# Qwiic_Haptic_Driver_DA7280.net
KiCad netlist of a schematic drawn in EAGLE
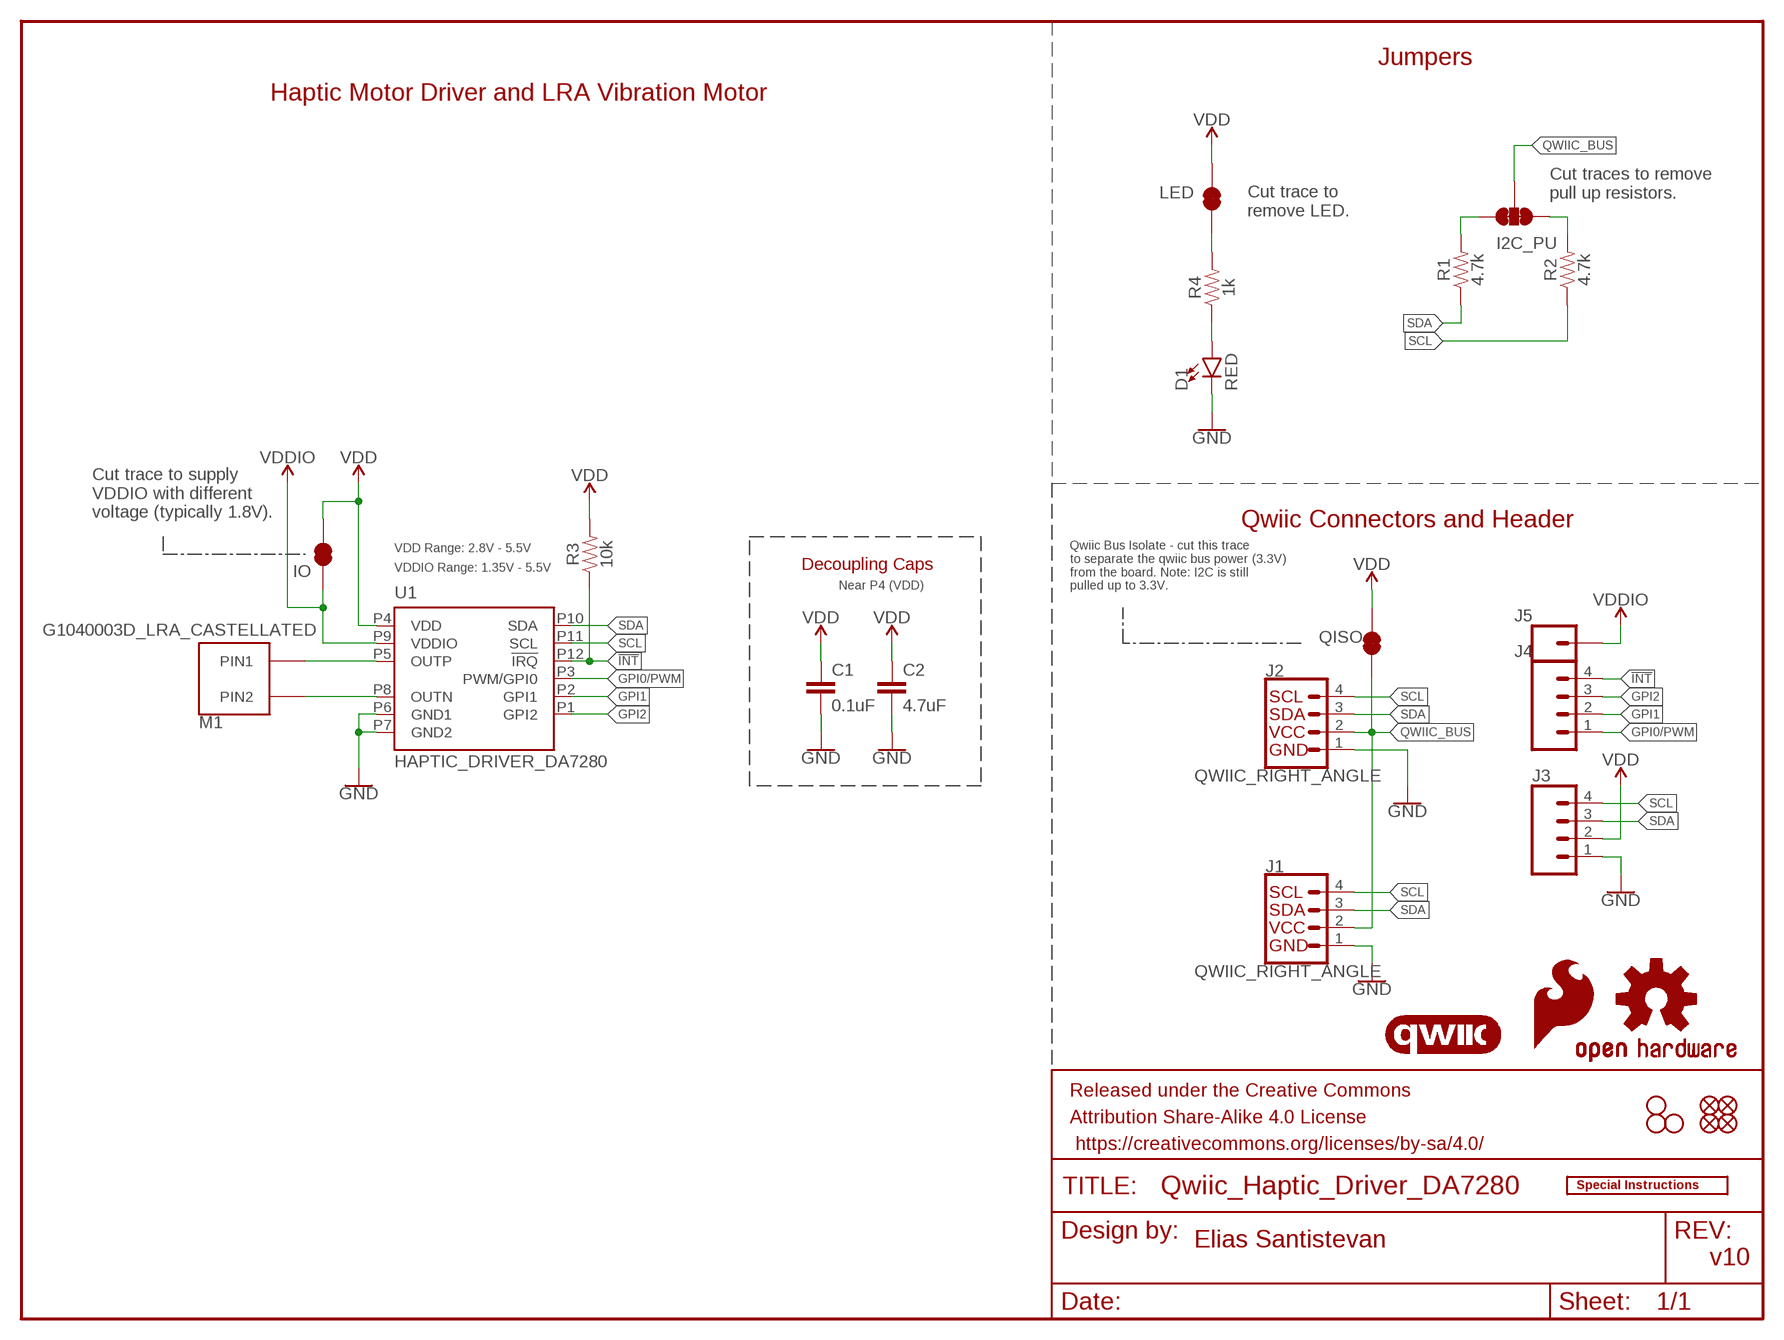
[diagram p0: schematic, sheet 1]

(export (version "E")
  (design (tool "Eeschema 10.0.6"))
  (components
    (comp (ref "C1")
      (value "0.1uF")
      (footprint "eagle-import:0603")
      (libsource (lib "eagle-import") (part "0.1UF-0603-25V-5%"))
    )
    (comp (ref "C2")
      (value "4.7uF")
      (footprint "eagle-import:0603")
      (libsource (lib "eagle-import") (part "4.7UF-0603-6.3V-(10%)"))
    )
    (comp (ref "D1")
      (value "RED")
      (footprint "eagle-import:LED-0603")
      (libsource (lib "eagle-import") (part "LED-RED0603"))
    )
    (comp (ref "FD1")
      (value "FIDUCIALUFIDUCIAL")
      (footprint "eagle-import:FIDUCIAL-MICRO")
      (libsource (lib "eagle-import") (part "FIDUCIALUFIDUCIAL"))
    )
    (comp (ref "FD2")
      (value "FIDUCIALUFIDUCIAL")
      (footprint "eagle-import:FIDUCIAL-MICRO")
      (libsource (lib "eagle-import") (part "FIDUCIALUFIDUCIAL"))
    )
    (comp (ref "FD3")
      (value "FIDUCIALUFIDUCIAL")
      (footprint "eagle-import:FIDUCIAL-MICRO")
      (libsource (lib "eagle-import") (part "FIDUCIALUFIDUCIAL"))
    )
    (comp (ref "FD4")
      (value "FIDUCIALUFIDUCIAL")
      (footprint "eagle-import:FIDUCIAL-MICRO")
      (libsource (lib "eagle-import") (part "FIDUCIALUFIDUCIAL"))
    )
    (comp (ref "FRAME1")
      (value "FRAME-LETTER")
      (footprint "eagle-import:CREATIVE_COMMONS")
      (libsource (lib "eagle-import") (part "FRAME-LETTER"))
    )
    (comp (ref "H1")
      (value "STAND-OFFTIGHT")
      (footprint "eagle-import:STAND-OFF-TIGHT")
      (libsource (lib "eagle-import") (part "STAND-OFFTIGHT"))
    )
    (comp (ref "H2")
      (value "STAND-OFFTIGHT")
      (footprint "eagle-import:STAND-OFF-TIGHT")
      (libsource (lib "eagle-import") (part "STAND-OFFTIGHT"))
    )
    (comp (ref "H4")
      (value "STAND-OFFTIGHT")
      (footprint "eagle-import:STAND-OFF-TIGHT")
      (libsource (lib "eagle-import") (part "STAND-OFFTIGHT"))
    )
    (comp (ref "J1")
      (value "QWIIC_RIGHT_ANGLE")
      (footprint "eagle-import:JST04_1MM_RA")
      (libsource (lib "eagle-import") (part "QWIIC_CONNECTORJS-1MM"))
    )
    (comp (ref "J2")
      (value "QWIIC_RIGHT_ANGLE")
      (footprint "eagle-import:JST04_1MM_RA")
      (libsource (lib "eagle-import") (part "QWIIC_CONNECTORJS-1MM"))
    )
    (comp (ref "J3")
      (value "CONN_041X04_NO_SILK_NO_POP")
      (footprint "eagle-import:1X04_NO_SILK")
      (libsource (lib "eagle-import") (part "CONN_041X04_NO_SILK_NO_POP"))
    )
    (comp (ref "J4")
      (value "CONN_041X04_NO_SILK_NO_POP")
      (footprint "eagle-import:1X04_NO_SILK")
      (libsource (lib "eagle-import") (part "CONN_041X04_NO_SILK_NO_POP"))
    )
    (comp (ref "J5")
      (value "CONN_01PTH_NO_SILK_YES_STOP")
      (footprint "eagle-import:1X01_NO_SILK")
      (libsource (lib "eagle-import") (part "CONN_01PTH_NO_SILK_YES_STOP"))
    )
    (comp (ref "JP1")
      (value "LED")
      (footprint "eagle-import:SMT-JUMPER_2_NC_TRACE_SILK")
      (libsource (lib "eagle-import") (part "JUMPER-SMT_2_NC_TRACE_SILK"))
    )
    (comp (ref "JP2")
      (value "LED")
      (footprint "eagle-import:SMT-JUMPER_2_NC_TRACE_SILK")
      (libsource (lib "eagle-import") (part "JUMPER-SMT_2_NC_TRACE_SILK"))
    )
    (comp (ref "JP3")
      (value "I2C_PU")
      (footprint "eagle-import:SMT-JUMPER_3_2-NC_TRACE_SILK")
      (libsource (lib "eagle-import") (part "JUMPER-SMT_3_2-NC_TRACE_SILK"))
    )
    (comp (ref "JP4")
      (value "LED")
      (footprint "eagle-import:SMT-JUMPER_2_NC_TRACE_SILK")
      (libsource (lib "eagle-import") (part "JUMPER-SMT_2_NC_TRACE_SILK"))
    )
    (comp (ref "LOGO1")
      (value "SPECIAL_INSTRUCTIONS-ORDERING")
      (footprint "eagle-import:ORDERING_INSTRUCTIONS")
      (libsource (lib "eagle-import") (part "SPECIAL_INSTRUCTIONS-ORDERING"))
    )
    (comp (ref "LOGO2")
      (value "OSHW-LOGOS")
      (footprint "eagle-import:OSHW-LOGO-S")
      (libsource (lib "eagle-import") (part "OSHW-LOGOS"))
    )
    (comp (ref "LOGO4")
      (value "SFE_LOGO_FLAME.1_INCH")
      (footprint "eagle-import:SFE_LOGO_FLAME_.1")
      (libsource (lib "eagle-import") (part "SFE_LOGO_FLAME.1_INCH"))
    )
    (comp (ref "M1")
      (value "G1040003D_LRA_CASTELLATED")
      (footprint "eagle-import:COIN_VIBRATION_MOTOR_CASTEL")
      (libsource (lib "eagle-import") (part "G1040003D_LRA_CASTELLATED"))
    )
    (comp (ref "R1")
      (value "4.7k")
      (footprint "eagle-import:0603")
      (libsource (lib "eagle-import") (part "4.7KOHM-0603-1/10W-1%"))
    )
    (comp (ref "R2")
      (value "4.7k")
      (footprint "eagle-import:0603")
      (libsource (lib "eagle-import") (part "4.7KOHM-0603-1/10W-1%"))
    )
    (comp (ref "R3")
      (value "10k")
      (footprint "eagle-import:0603")
      (libsource (lib "eagle-import") (part "10KOHM-0603-1/10W-1%"))
    )
    (comp (ref "R4")
      (value "1k")
      (footprint "eagle-import:0603")
      (libsource (lib "eagle-import") (part "1KOHM-0603-1/10W-1%"))
    )
    (comp (ref "U$1")
      (value "QWIIC_LOGO_3MM")
      (footprint "eagle-import:QWIIC_3MM")
      (libsource (lib "eagle-import") (part "QWIIC_LOGO_3MM"))
    )
    (comp (ref "U1")
      (value "HAPTIC_DRIVER_DA7280")
      (footprint "eagle-import:QFN_DA7280")
      (libsource (lib "eagle-import") (part "HAPTIC_DRIVER_DA7280"))
    )
  )
  (nets
    (net (code "1") (name "/~{INT}") (class "Default")
      (node (ref "J4") (pin "4") (pinfunction "4_4") (pintype "passive"))
      (node (ref "R3") (pin "1") (pinfunction "1_1") (pintype "passive"))
      (node (ref "U1") (pin "P12") (pinfunction "~{IRQ}_P12") (pintype "output"))
    )
    (net (code "2") (name "GND") (class "Default")
      (node (ref "C1") (pin "2") (pinfunction "2_2") (pintype "passive"))
      (node (ref "C2") (pin "2") (pinfunction "2_2") (pintype "passive"))
      (node (ref "D1") (pin "C") (pinfunction "C_C") (pintype "passive"))
      (node (ref "J1") (pin "1") (pinfunction "1_1") (pintype "power_in"))
      (node (ref "J2") (pin "1") (pinfunction "1_1") (pintype "power_in"))
      (node (ref "J3") (pin "1") (pinfunction "1_1") (pintype "passive"))
      (node (ref "U1") (pin "P6") (pinfunction "GND1_P6") (pintype "power_in"))
      (node (ref "U1") (pin "P7") (pinfunction "GND2_P7") (pintype "power_in"))
    )
    (net (code "3") (name "GPI0{slash}PWM") (class "Default")
      (node (ref "J4") (pin "1") (pinfunction "1_1") (pintype "passive"))
      (node (ref "U1") (pin "P3") (pinfunction "PWM/GPI0_P3") (pintype "input"))
    )
    (net (code "4") (name "GPI1") (class "Default")
      (node (ref "J4") (pin "2") (pinfunction "2_2") (pintype "passive"))
      (node (ref "U1") (pin "P2") (pinfunction "GPI1_P2") (pintype "input"))
    )
    (net (code "5") (name "GPI2") (class "Default")
      (node (ref "J4") (pin "3") (pinfunction "3_3") (pintype "passive"))
      (node (ref "U1") (pin "P1") (pinfunction "GPI2_P1") (pintype "input"))
    )
    (net (code "6") (name "Net-(D1-PadA)") (class "Default")
      (node (ref "D1") (pin "A") (pinfunction "A_A") (pintype "passive"))
      (node (ref "R4") (pin "1") (pinfunction "1_1") (pintype "passive"))
    )
    (net (code "7") (name "Net-(JP1-Pad1)") (class "Default")
      (node (ref "JP1") (pin "1") (pinfunction "1_1") (pintype "passive"))
      (node (ref "R4") (pin "2") (pinfunction "2_2") (pintype "passive"))
    )
    (net (code "8") (name "Net-(JP3-Pad1)") (class "Default")
      (node (ref "JP3") (pin "1") (pinfunction "1_1") (pintype "passive"))
      (node (ref "R2") (pin "2") (pinfunction "2_2") (pintype "passive"))
    )
    (net (code "9") (name "Net-(JP3-Pad3)") (class "Default")
      (node (ref "JP3") (pin "3") (pinfunction "3_3") (pintype "passive"))
      (node (ref "R1") (pin "2") (pinfunction "2_2") (pintype "passive"))
    )
    (net (code "10") (name "Net-(M1-PIN1)") (class "Default")
      (node (ref "M1") (pin "P$1") (pinfunction "PIN1_P$1") (pintype "bidirectional"))
      (node (ref "U1") (pin "P5") (pinfunction "OUTP_P5") (pintype "output"))
    )
    (net (code "11") (name "Net-(M1-PIN2)") (class "Default")
      (node (ref "M1") (pin "P$2") (pinfunction "PIN2_P$2") (pintype "bidirectional"))
      (node (ref "U1") (pin "P8") (pinfunction "OUTN_P8") (pintype "output"))
    )
    (net (code "12") (name "QWIIC_BUS") (class "Default")
      (node (ref "J1") (pin "2") (pinfunction "2_2") (pintype "power_in"))
      (node (ref "J2") (pin "2") (pinfunction "2_2") (pintype "power_in"))
      (node (ref "JP3") (pin "2") (pinfunction "2_2") (pintype "passive"))
      (node (ref "JP4") (pin "1") (pinfunction "1_1") (pintype "passive"))
    )
    (net (code "13") (name "SCL") (class "Default")
      (node (ref "J1") (pin "4") (pinfunction "4_4") (pintype "passive"))
      (node (ref "J2") (pin "4") (pinfunction "4_4") (pintype "passive"))
      (node (ref "J3") (pin "4") (pinfunction "4_4") (pintype "passive"))
      (node (ref "R2") (pin "1") (pinfunction "1_1") (pintype "passive"))
      (node (ref "U1") (pin "P11") (pinfunction "SCL_P11") (pintype "bidirectional"))
    )
    (net (code "14") (name "SDA") (class "Default")
      (node (ref "J1") (pin "3") (pinfunction "3_3") (pintype "passive"))
      (node (ref "J2") (pin "3") (pinfunction "3_3") (pintype "passive"))
      (node (ref "J3") (pin "3") (pinfunction "3_3") (pintype "passive"))
      (node (ref "R1") (pin "1") (pinfunction "1_1") (pintype "passive"))
      (node (ref "U1") (pin "P10") (pinfunction "SDA_P10") (pintype "bidirectional"))
    )
    (net (code "15") (name "VDD") (class "Default")
      (node (ref "C1") (pin "1") (pinfunction "1_1") (pintype "passive"))
      (node (ref "C2") (pin "1") (pinfunction "1_1") (pintype "passive"))
      (node (ref "J3") (pin "2") (pinfunction "2_2") (pintype "passive"))
      (node (ref "JP1") (pin "2") (pinfunction "2_2") (pintype "passive"))
      (node (ref "JP2") (pin "2") (pinfunction "2_2") (pintype "passive"))
      (node (ref "JP4") (pin "2") (pinfunction "2_2") (pintype "passive"))
      (node (ref "R3") (pin "2") (pinfunction "2_2") (pintype "passive"))
      (node (ref "U1") (pin "P4") (pinfunction "VDD_P4") (pintype "power_in"))
    )
    (net (code "16") (name "VDDIO") (class "Default")
      (node (ref "J5") (pin "1") (pinfunction "1_1") (pintype "passive"))
      (node (ref "JP2") (pin "1") (pinfunction "1_1") (pintype "passive"))
      (node (ref "U1") (pin "P9") (pinfunction "VDDIO_P9") (pintype "power_in"))
    )
  )
)
